# RPi-HAT_BUS-Controller_V0_8.net
KiCad netlist of a schematic drawn in EAGLE
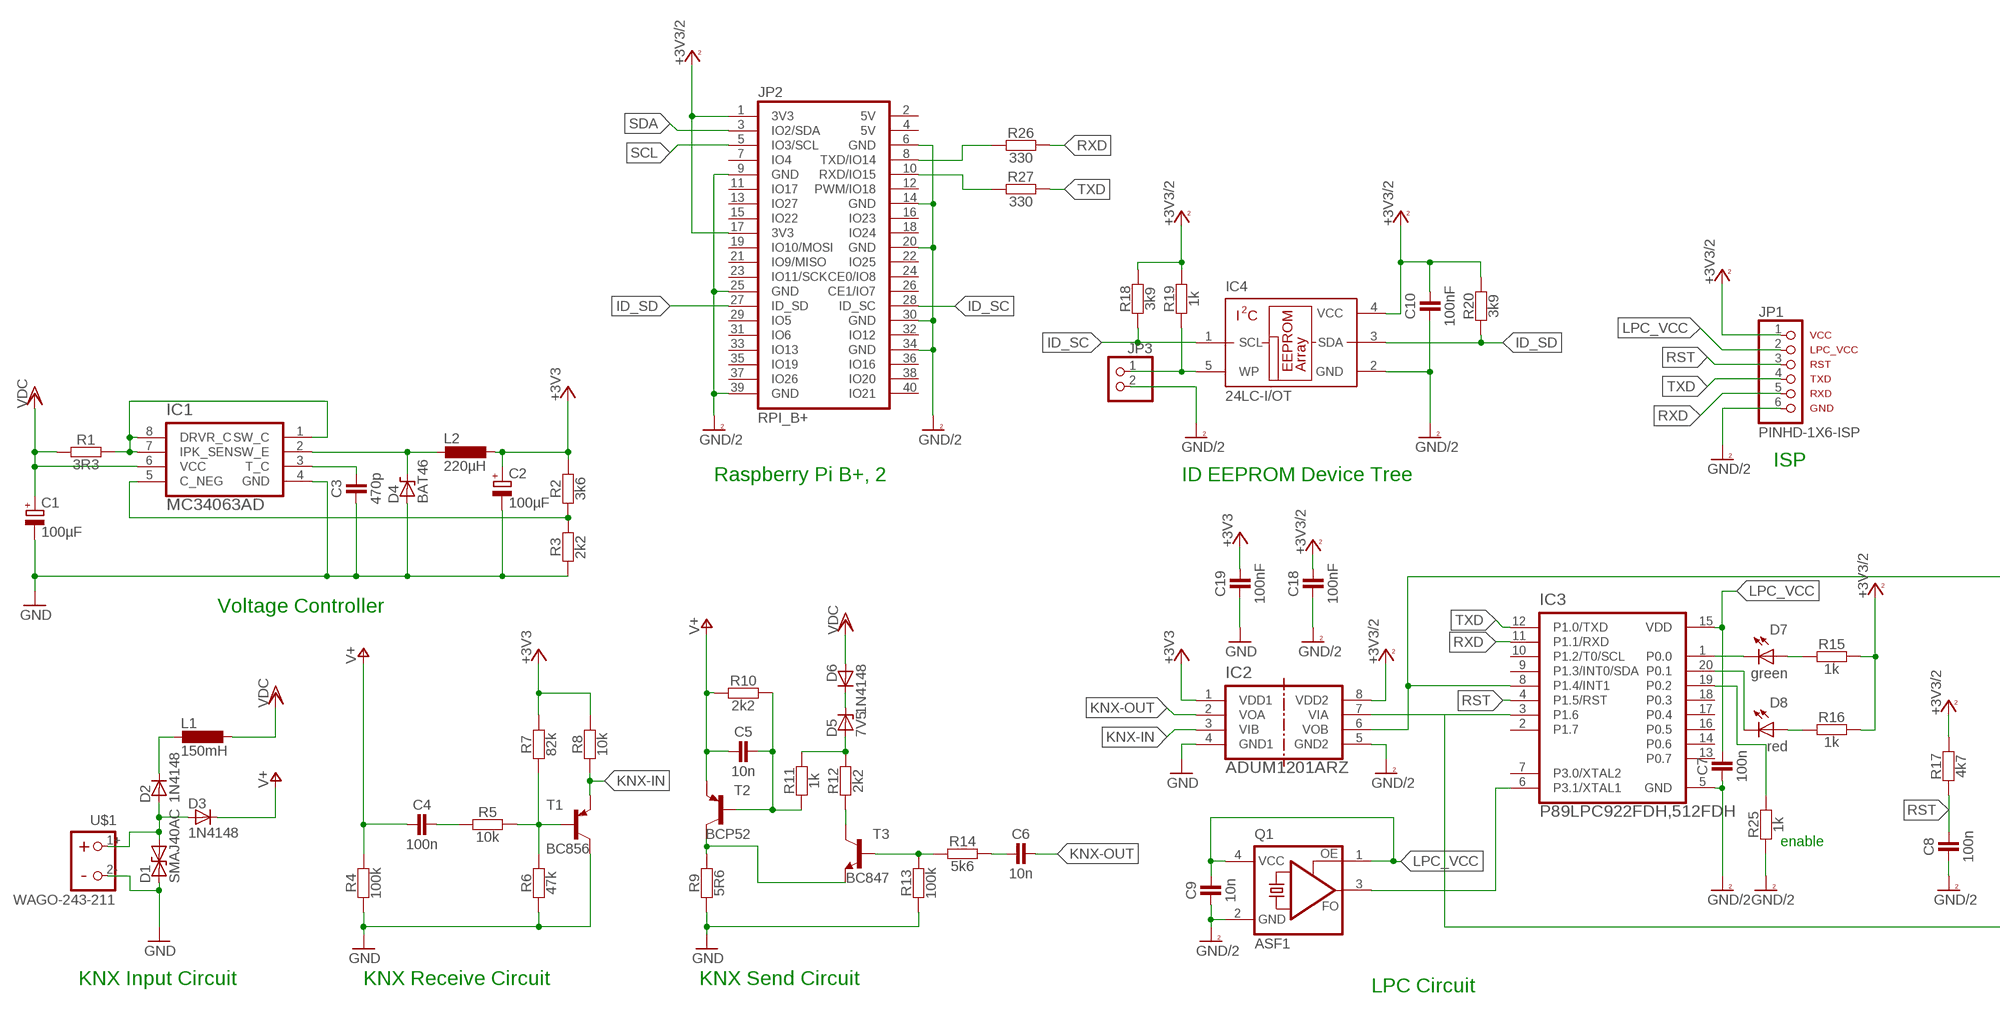
[diagram p0: schematic, sheet 1, part 1 of 2]
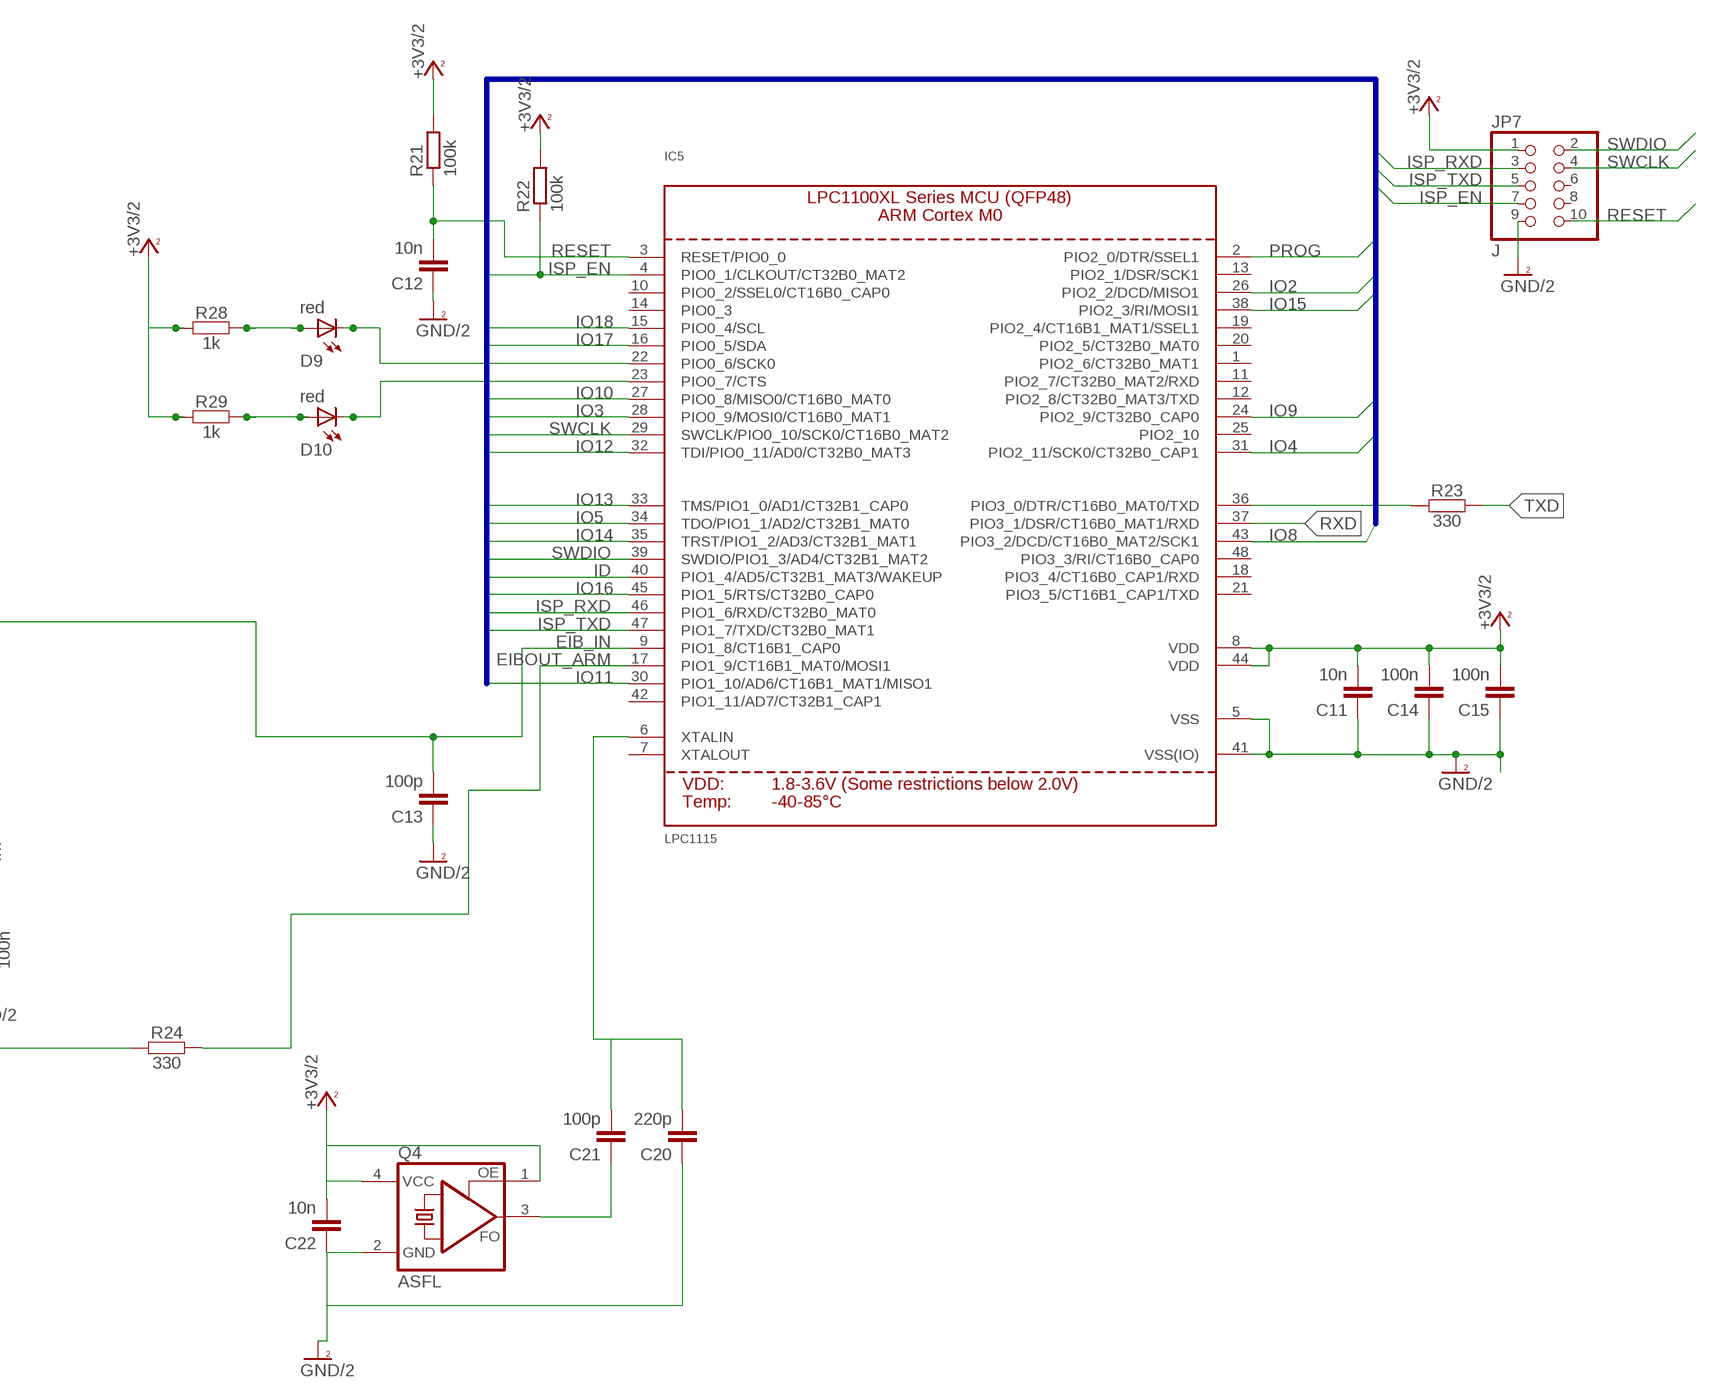
[diagram p1: schematic, sheet 1, part 2 of 2]

(export (version "E")
  (design (tool "Eeschema 10.0.6"))
  (components
    (comp (ref "C1")
      (value "100µF")
      (footprint "eagle-import:PANASONIC_D")
      (libsource (lib "eagle-import") (part "100µF,35V"))
    )
    (comp (ref "C2")
      (value "100µF")
      (footprint "eagle-import:PANASONIC_C")
      (libsource (lib "eagle-import") (part "100µF,6.3V"))
    )
    (comp (ref "C3")
      (value "470p")
      (footprint "eagle-import:R1206")
      (libsource (lib "eagle-import") (part "CAPACITORC1206"))
    )
    (comp (ref "C4")
      (value "100n")
      (footprint "eagle-import:R1206")
      (libsource (lib "eagle-import") (part "CAPACITORC1206"))
    )
    (comp (ref "C5")
      (value "10n")
      (footprint "eagle-import:R1206")
      (libsource (lib "eagle-import") (part "CAPACITORC1206"))
    )
    (comp (ref "C6")
      (value "10n")
      (footprint "eagle-import:R1206")
      (libsource (lib "eagle-import") (part "CAPACITORC1206"))
    )
    (comp (ref "C7")
      (value "100n")
      (footprint "eagle-import:R1206")
      (libsource (lib "eagle-import") (part "CAPACITORC1206"))
    )
    (comp (ref "C8")
      (value "100n")
      (footprint "eagle-import:R1206")
      (libsource (lib "eagle-import") (part "CAPACITORC1206"))
    )
    (comp (ref "C9")
      (value "10n")
      (footprint "eagle-import:R1206")
      (libsource (lib "eagle-import") (part "CAPACITORC1206"))
    )
    (comp (ref "C10")
      (value "100nF")
      (footprint "eagle-import:R1206")
      (libsource (lib "eagle-import") (part "CAPACITORC1206"))
    )
    (comp (ref "C11")
      (value "10n")
      (footprint "eagle-import:C1206")
      (libsource (lib "eagle-import") (part "C-EUC1206"))
    )
    (comp (ref "C12")
      (value "10n")
      (footprint "eagle-import:C1206")
      (libsource (lib "eagle-import") (part "C-EUC1206"))
    )
    (comp (ref "C13")
      (value "100p")
      (footprint "eagle-import:C1206")
      (libsource (lib "eagle-import") (part "C-EUC1206"))
    )
    (comp (ref "C14")
      (value "100n")
      (footprint "eagle-import:C1206")
      (libsource (lib "eagle-import") (part "C-EUC1206"))
    )
    (comp (ref "C15")
      (value "100n")
      (footprint "eagle-import:C1206")
      (libsource (lib "eagle-import") (part "C-EUC1206"))
    )
    (comp (ref "C18")
      (value "100nF")
      (footprint "eagle-import:R1206")
      (libsource (lib "eagle-import") (part "CAPACITORC1206"))
    )
    (comp (ref "C19")
      (value "100nF")
      (footprint "eagle-import:R1206")
      (libsource (lib "eagle-import") (part "CAPACITORC1206"))
    )
    (comp (ref "C20")
      (value "220p")
      (footprint "eagle-import:C1206")
      (libsource (lib "eagle-import") (part "C-EUC1206"))
    )
    (comp (ref "C21")
      (value "100p")
      (footprint "eagle-import:C1206")
      (libsource (lib "eagle-import") (part "C-EUC1206"))
    )
    (comp (ref "C22")
      (value "10n")
      (footprint "eagle-import:C1206")
      (libsource (lib "eagle-import") (part "C-EUC1206"))
    )
    (comp (ref "D1")
      (value "SMAJ40AC")
      (footprint "eagle-import:DO-214AC")
      (libsource (lib "eagle-import") (part "SMAJ40AC"))
    )
    (comp (ref "D2")
      (value "1N4148")
      (footprint "eagle-import:MINIMELF")
      (libsource (lib "eagle-import") (part "1N4148MINIMELF"))
    )
    (comp (ref "D3")
      (value "1N4148")
      (footprint "eagle-import:MINIMELF")
      (libsource (lib "eagle-import") (part "1N4148MINIMELF"))
    )
    (comp (ref "D4")
      (value "BAT46")
      (footprint "eagle-import:MINIMELF")
      (libsource (lib "eagle-import") (part "BAT46"))
    )
    (comp (ref "D5")
      (value "7V5")
      (footprint "eagle-import:MINIMELF")
      (libsource (lib "eagle-import") (part "Z-DIODE"))
    )
    (comp (ref "D6")
      (value "1N4148")
      (footprint "eagle-import:MINIMELF")
      (libsource (lib "eagle-import") (part "Diode_for_Selfbus-Projects_1N4148MINIMELF"))
    )
    (comp (ref "D7")
      (value "green")
      (footprint "eagle-import:CHIPLED_1206")
      (libsource (lib "eagle-import") (part "LED1206"))
    )
    (comp (ref "D8")
      (value "red")
      (footprint "eagle-import:CHIPLED_1206")
      (libsource (lib "eagle-import") (part "LED1206"))
    )
    (comp (ref "D9")
      (value "red")
      (footprint "eagle-import:CHIPLED_1206")
      (libsource (lib "eagle-import") (part "LED1206"))
    )
    (comp (ref "D10")
      (value "red")
      (footprint "eagle-import:CHIPLED_1206")
      (libsource (lib "eagle-import") (part "LED1206"))
    )
    (comp (ref "IC1")
      (value "MC34063AD")
      (footprint "eagle-import:SOIC127P600X175-8N")
      (libsource (lib "eagle-import") (part "MC34063AD"))
    )
    (comp (ref "IC2")
      (value "ADUM1201ARZ")
      (footprint "eagle-import:SOIC127P600X175-8N")
      (libsource (lib "eagle-import") (part "ADUM1201ARZ"))
    )
    (comp (ref "IC3")
      (value "P89LPC922FDH,512FDH")
      (footprint "eagle-import:SOP65P640X110-20N")
      (fields (field (name "MPN") "P89LPC922FDH,512"))
      (libsource (lib "eagle-import") (part "P89LPC922FDH,512FDH"))
    )
    (comp (ref "IC4")
      (value "24LC-I/OT")
      (footprint "eagle-import:SOT23-5")
      (libsource (lib "eagle-import") (part "24LC-I/OT"))
    )
    (comp (ref "IC5")
      (value "LPC1115")
      (footprint "eagle-import:LQFP48")
      (libsource (lib "eagle-import") (part "LPC1113/4/5_QFP48_XLSERIES"))
    )
    (comp (ref "JP1")
      (value "PINHD-1X6-ISP")
      (footprint "eagle-import:1X06")
      (libsource (lib "eagle-import") (part "PINHD-1X6-ISP"))
    )
    (comp (ref "JP2")
      (value "RPI_B+")
      (footprint "eagle-import:RPI-B+HAT")
      (libsource (lib "eagle-import") (part "RPI_B+"))
    )
    (comp (ref "JP3")
      (value "PINHD-1X2")
      (footprint "eagle-import:1X02")
      (libsource (lib "eagle-import") (part "PINHD-1X2"))
    )
    (comp (ref "JP7")
      (value "J")
      (footprint "eagle-import:2X05M")
      (libsource (lib "eagle-import") (part "PINHD-2X05_2.00"))
    )
    (comp (ref "L1")
      (value "150mH")
      (footprint "eagle-import:11P-L1")
      (libsource (lib "eagle-import") (part "150MH-L11PL1"))
    )
    (comp (ref "L2")
      (value "220µH")
      (footprint "eagle-import:2200-11.43")
      (libsource (lib "eagle-import") (part "220µH-SMCC11.43"))
    )
    (comp (ref "Q1")
      (value "ASF1")
      (footprint "eagle-import:ASF")
      (libsource (lib "eagle-import") (part "ASF1"))
    )
    (comp (ref "Q4")
      (value "ASFL")
      (footprint "eagle-import:ASF")
      (fields (field (name "MPN") "ASFLM1-50.000MHZ-C-T"))
      (libsource (lib "eagle-import") (part "crystal_ASFL"))
    )
    (comp (ref "R1")
      (value "3R3")
      (footprint "eagle-import:R1206")
      (libsource (lib "eagle-import") (part "RESISTORR1206"))
    )
    (comp (ref "R2")
      (value "3k6")
      (footprint "eagle-import:R1206")
      (libsource (lib "eagle-import") (part "RESISTORR1206"))
    )
    (comp (ref "R3")
      (value "2k2")
      (footprint "eagle-import:R1206")
      (libsource (lib "eagle-import") (part "RESISTORR1206"))
    )
    (comp (ref "R4")
      (value "100k")
      (footprint "eagle-import:R1206")
      (libsource (lib "eagle-import") (part "RESISTORR1206"))
    )
    (comp (ref "R5")
      (value "10k")
      (footprint "eagle-import:R1206")
      (libsource (lib "eagle-import") (part "RESISTORR1206"))
    )
    (comp (ref "R6")
      (value "47k")
      (footprint "eagle-import:R1206")
      (libsource (lib "eagle-import") (part "RESISTORR1206"))
    )
    (comp (ref "R7")
      (value "82k")
      (footprint "eagle-import:R1206")
      (libsource (lib "eagle-import") (part "RESISTORR1206"))
    )
    (comp (ref "R8")
      (value "10k")
      (footprint "eagle-import:R1206")
      (libsource (lib "eagle-import") (part "RESISTORR1206"))
    )
    (comp (ref "R9")
      (value "5R6")
      (footprint "eagle-import:R1206")
      (libsource (lib "eagle-import") (part "RESISTORR1206"))
    )
    (comp (ref "R10")
      (value "2k2")
      (footprint "eagle-import:R1206")
      (libsource (lib "eagle-import") (part "RESISTORR1206"))
    )
    (comp (ref "R11")
      (value "1k")
      (footprint "eagle-import:R1206")
      (libsource (lib "eagle-import") (part "RESISTORR1206"))
    )
    (comp (ref "R12")
      (value "2k2")
      (footprint "eagle-import:R1206")
      (libsource (lib "eagle-import") (part "RESISTORR1206"))
    )
    (comp (ref "R13")
      (value "100k")
      (footprint "eagle-import:R1206")
      (libsource (lib "eagle-import") (part "RESISTORR1206"))
    )
    (comp (ref "R14")
      (value "5k6")
      (footprint "eagle-import:R1206")
      (libsource (lib "eagle-import") (part "RESISTORR1206"))
    )
    (comp (ref "R15")
      (value "1k")
      (footprint "eagle-import:R1206")
      (libsource (lib "eagle-import") (part "RESISTORR1206"))
    )
    (comp (ref "R16")
      (value "1k")
      (footprint "eagle-import:R1206")
      (libsource (lib "eagle-import") (part "RESISTORR1206"))
    )
    (comp (ref "R17")
      (value "4k7")
      (footprint "eagle-import:R1206")
      (libsource (lib "eagle-import") (part "RESISTORR1206"))
    )
    (comp (ref "R18")
      (value "3k9")
      (footprint "eagle-import:R1206")
      (libsource (lib "eagle-import") (part "RESISTORR1206"))
    )
    (comp (ref "R19")
      (value "1k")
      (footprint "eagle-import:R1206")
      (libsource (lib "eagle-import") (part "RESISTORR1206"))
    )
    (comp (ref "R20")
      (value "3k9")
      (footprint "eagle-import:R1206")
      (libsource (lib "eagle-import") (part "RESISTORR1206"))
    )
    (comp (ref "R21")
      (value "100k")
      (footprint "eagle-import:R1206")
      (libsource (lib "eagle-import") (part "R-EU_R1206"))
    )
    (comp (ref "R22")
      (value "100k")
      (footprint "eagle-import:R1206")
      (libsource (lib "eagle-import") (part "R-EU_R1206"))
    )
    (comp (ref "R23")
      (value "330")
      (footprint "eagle-import:R1206")
      (libsource (lib "eagle-import") (part "RESISTORR1206"))
    )
    (comp (ref "R24")
      (value "330")
      (footprint "eagle-import:R1206")
      (libsource (lib "eagle-import") (part "RESISTORR1206"))
    )
    (comp (ref "R25")
      (value "1k")
      (footprint "eagle-import:R1206")
      (libsource (lib "eagle-import") (part "RESISTORR1206"))
    )
    (comp (ref "R26")
      (value "330")
      (footprint "eagle-import:R1206")
      (libsource (lib "eagle-import") (part "RESISTORR1206"))
    )
    (comp (ref "R27")
      (value "330")
      (footprint "eagle-import:R1206")
      (libsource (lib "eagle-import") (part "RESISTORR1206"))
    )
    (comp (ref "R28")
      (value "1k")
      (footprint "eagle-import:R1206")
      (libsource (lib "eagle-import") (part "RESISTORR1206"))
    )
    (comp (ref "R29")
      (value "1k")
      (footprint "eagle-import:R1206")
      (libsource (lib "eagle-import") (part "RESISTORR1206"))
    )
    (comp (ref "T1")
      (value "BC856")
      (footprint "eagle-import:SOT23")
      (libsource (lib "eagle-import") (part "PNPBC856"))
    )
    (comp (ref "T2")
      (value "BCP52")
      (footprint "eagle-import:SOT223")
      (libsource (lib "eagle-import") (part "PNPBCP52"))
    )
    (comp (ref "T3")
      (value "BC847")
      (footprint "eagle-import:SOT23")
      (libsource (lib "eagle-import") (part "NPN-BC847"))
    )
    (comp (ref "U$1")
      (value "WAGO-243-211")
      (footprint "eagle-import:WAGO-243-211")
      (libsource (lib "eagle-import") (part "WAGO-243-211"))
    )
  )
  (nets
    (net (code "1") (name "+3V3") (class "Default")
      (node (ref "C19") (pin "2") (pinfunction "2_2") (pintype "passive"))
      (node (ref "C2") (pin "+") (pinfunction "+_+") (pintype "passive"))
      (node (ref "IC2") (pin "1") (pinfunction "VDD1_1") (pintype "power_in"))
      (node (ref "L2") (pin "1") (pinfunction "1_1") (pintype "passive"))
      (node (ref "R2") (pin "2") (pinfunction "2_2") (pintype "passive"))
      (node (ref "R7") (pin "2") (pinfunction "2_2") (pintype "passive"))
      (node (ref "R8") (pin "2") (pinfunction "2_2") (pintype "passive"))
    )
    (net (code "2") (name "+3V3{slash}2") (class "Default")
      (node (ref "C10") (pin "2") (pinfunction "2_2") (pintype "passive"))
      (node (ref "C11") (pin "2") (pinfunction "2_2") (pintype "passive"))
      (node (ref "C14") (pin "2") (pinfunction "2_2") (pintype "passive"))
      (node (ref "C15") (pin "2") (pinfunction "2_2") (pintype "passive"))
      (node (ref "C18") (pin "2") (pinfunction "2_2") (pintype "passive"))
      (node (ref "C22") (pin "2") (pinfunction "2_2") (pintype "passive"))
      (node (ref "IC2") (pin "8") (pinfunction "VDD2_8") (pintype "power_in"))
      (node (ref "IC4") (pin "4") (pinfunction "VCC_4") (pintype "power_in"))
      (node (ref "IC5") (pin "44") (pinfunction "VDD_44") (pintype "power_in"))
      (node (ref "IC5") (pin "8") (pinfunction "VDD_8") (pintype "power_in"))
      (node (ref "JP1") (pin "1") (pinfunction "1_1") (pintype "passive"))
      (node (ref "JP2") (pin "1") (pinfunction "3V3_1") (pintype "passive"))
      (node (ref "JP2") (pin "17") (pinfunction "3V3_17") (pintype "passive"))
      (node (ref "JP7") (pin "1") (pinfunction "1_1") (pintype "passive"))
      (node (ref "Q4") (pin "1") (pinfunction "OE_1") (pintype "input"))
      (node (ref "Q4") (pin "4") (pinfunction "VCC_4") (pintype "power_in"))
      (node (ref "R15") (pin "2") (pinfunction "2_2") (pintype "passive"))
      (node (ref "R16") (pin "2") (pinfunction "2_2") (pintype "passive"))
      (node (ref "R17") (pin "2") (pinfunction "2_2") (pintype "passive"))
      (node (ref "R18") (pin "2") (pinfunction "2_2") (pintype "passive"))
      (node (ref "R19") (pin "2") (pinfunction "2_2") (pintype "passive"))
      (node (ref "R20") (pin "2") (pinfunction "2_2") (pintype "passive"))
      (node (ref "R21") (pin "2") (pinfunction "2_2") (pintype "passive"))
      (node (ref "R22") (pin "2") (pinfunction "2_2") (pintype "passive"))
      (node (ref "R28") (pin "1") (pinfunction "1_1") (pintype "passive"))
      (node (ref "R29") (pin "1") (pinfunction "1_1") (pintype "passive"))
    )
    (net (code "3") (name "/EIBOUT_ARM") (class "Default")
      (node (ref "IC5") (pin "17") (pinfunction "PIO1_9/CT16B1_MAT0/MOSI1_17") (pintype "bidirectional"))
      (node (ref "R24") (pin "2") (pinfunction "2_2") (pintype "passive"))
    )
    (net (code "4") (name "/EIB_IN") (class "Default")
      (node (ref "C13") (pin "2") (pinfunction "2_2") (pintype "passive"))
      (node (ref "IC2") (pin "6") (pinfunction "VOB_6") (pintype "output"))
      (node (ref "IC3") (pin "8") (pinfunction "P1.4/INT1_8") (pintype "bidirectional"))
      (node (ref "IC5") (pin "9") (pinfunction "PIO1_8/CT16B1_CAP0_9") (pintype "bidirectional"))
    )
    (net (code "5") (name "/ID") (class "Default")
      (node (ref "IC5") (pin "40") (pinfunction "PIO1_4/AD5/CT32B1_MAT3/WAKEUP_40") (pintype "bidirectional"))
    )
    (net (code "6") (name "/IO2") (class "Default")
      (node (ref "IC5") (pin "26") (pinfunction "PIO2_2/DCD/MISO1_26") (pintype "bidirectional"))
    )
    (net (code "7") (name "/IO3") (class "Default")
      (node (ref "IC5") (pin "28") (pinfunction "PIO0_9/MOSI0/CT16B0_MAT1_28") (pintype "bidirectional"))
    )
    (net (code "8") (name "/IO4") (class "Default")
      (node (ref "IC5") (pin "31") (pinfunction "PIO2_11/SCK0/CT32B0_CAP1_31") (pintype "bidirectional"))
    )
    (net (code "9") (name "/IO5") (class "Default")
      (node (ref "IC5") (pin "34") (pinfunction "TDO/PIO1_1/AD2/CT32B1_MAT0_34") (pintype "bidirectional"))
    )
    (net (code "10") (name "/IO8") (class "Default")
      (node (ref "IC5") (pin "43") (pinfunction "PIO3_2/DCD/CT16B0_MAT2/SCK1_43") (pintype "bidirectional"))
    )
    (net (code "11") (name "/IO9") (class "Default")
      (node (ref "IC5") (pin "24") (pinfunction "PIO2_9/CT32B0_CAP0_24") (pintype "bidirectional"))
    )
    (net (code "12") (name "/IO10") (class "Default")
      (node (ref "IC5") (pin "27") (pinfunction "PIO0_8/MISO0/CT16B0_MAT0_27") (pintype "bidirectional"))
    )
    (net (code "13") (name "/IO11") (class "Default")
      (node (ref "IC5") (pin "30") (pinfunction "PIO1_10/AD6/CT16B1_MAT1/MISO1_30") (pintype "bidirectional"))
    )
    (net (code "14") (name "/IO12") (class "Default")
      (node (ref "IC5") (pin "32") (pinfunction "TDI/PIO0_11/AD0/CT32B0_MAT3_32") (pintype "bidirectional"))
    )
    (net (code "15") (name "/IO13") (class "Default")
      (node (ref "IC5") (pin "33") (pinfunction "TMS/PIO1_0/AD1/CT32B1_CAP0_33") (pintype "bidirectional"))
    )
    (net (code "16") (name "/IO14") (class "Default")
      (node (ref "IC5") (pin "35") (pinfunction "TRST/PIO1_2/AD3/CT32B1_MAT1_35") (pintype "bidirectional"))
    )
    (net (code "17") (name "/IO15") (class "Default")
      (node (ref "IC5") (pin "38") (pinfunction "PIO2_3/RI/MOSI1_38") (pintype "bidirectional"))
    )
    (net (code "18") (name "/IO16") (class "Default")
      (node (ref "IC5") (pin "45") (pinfunction "PIO1_5/RTS/CT32B0_CAP0_45") (pintype "bidirectional"))
    )
    (net (code "19") (name "/IO17") (class "Default")
      (node (ref "IC5") (pin "16") (pinfunction "PIO0_5/SDA_16") (pintype "bidirectional"))
    )
    (net (code "20") (name "/IO18") (class "Default")
      (node (ref "IC5") (pin "15") (pinfunction "PIO0_4/SCL_15") (pintype "bidirectional"))
    )
    (net (code "21") (name "/ISP_EN") (class "Default")
      (node (ref "IC5") (pin "4") (pinfunction "PIO0_1/CLKOUT/CT32B0_MAT2_4") (pintype "bidirectional"))
      (node (ref "JP7") (pin "7") (pinfunction "7_7") (pintype "passive"))
      (node (ref "R22") (pin "1") (pinfunction "1_1") (pintype "passive"))
    )
    (net (code "22") (name "/ISP_RXD") (class "Default")
      (node (ref "IC5") (pin "46") (pinfunction "PIO1_6/RXD/CT32B0_MAT0_46") (pintype "bidirectional"))
      (node (ref "JP7") (pin "3") (pinfunction "3_3") (pintype "passive"))
    )
    (net (code "23") (name "/ISP_TXD") (class "Default")
      (node (ref "IC5") (pin "47") (pinfunction "PIO1_7/TXD/CT32B0_MAT1_47") (pintype "bidirectional"))
      (node (ref "JP7") (pin "5") (pinfunction "5_5") (pintype "passive"))
    )
    (net (code "24") (name "/PROG") (class "Default")
      (node (ref "IC5") (pin "2") (pinfunction "PIO2_0/DTR/SSEL1_2") (pintype "bidirectional"))
    )
    (net (code "25") (name "/RESET") (class "Default")
      (node (ref "C12") (pin "2") (pinfunction "2_2") (pintype "passive"))
      (node (ref "IC5") (pin "3") (pinfunction "RESET/PIO0_0_3") (pintype "bidirectional"))
      (node (ref "JP7") (pin "10") (pinfunction "10_10") (pintype "passive"))
      (node (ref "R21") (pin "1") (pinfunction "1_1") (pintype "passive"))
    )
    (net (code "26") (name "/SWCLK") (class "Default")
      (node (ref "IC5") (pin "29") (pinfunction "SWCLK/PIO0_10/SCK0/CT16B0_MAT2_29") (pintype "bidirectional"))
      (node (ref "JP7") (pin "4") (pinfunction "4_4") (pintype "passive"))
    )
    (net (code "27") (name "/SWDIO") (class "Default")
      (node (ref "IC5") (pin "39") (pinfunction "SWDIO/PIO1_3/AD4/CT32B1_MAT2_39") (pintype "bidirectional"))
      (node (ref "JP7") (pin "2") (pinfunction "2_2") (pintype "passive"))
    )
    (net (code "28") (name "GND") (class "Default")
      (node (ref "C1") (pin "-") (pinfunction "-_-") (pintype "passive"))
      (node (ref "C19") (pin "1") (pinfunction "1_1") (pintype "passive"))
      (node (ref "C2") (pin "-") (pinfunction "-_-") (pintype "passive"))
      (node (ref "C3") (pin "1") (pinfunction "1_1") (pintype "passive"))
      (node (ref "D1") (pin "A") (pinfunction "A_A") (pintype "passive"))
      (node (ref "D4") (pin "A") (pinfunction "A_A") (pintype "passive"))
      (node (ref "IC1") (pin "4") (pinfunction "GND_4") (pintype "passive"))
      (node (ref "IC2") (pin "4") (pinfunction "GND1_4") (pintype "passive"))
      (node (ref "R13") (pin "1") (pinfunction "1_1") (pintype "passive"))
      (node (ref "R3") (pin "1") (pinfunction "1_1") (pintype "passive"))
      (node (ref "R4") (pin "1") (pinfunction "1_1") (pintype "passive"))
      (node (ref "R6") (pin "1") (pinfunction "1_1") (pintype "passive"))
      (node (ref "R9") (pin "1") (pinfunction "1_1") (pintype "passive"))
      (node (ref "T1") (pin "3") (pinfunction "C_3") (pintype "passive"))
      (node (ref "U$1") (pin "2-") (pinfunction "2-_2-") (pintype "passive"))
    )
    (net (code "29") (name "GND{slash}2") (class "Default")
      (node (ref "C10") (pin "1") (pinfunction "1_1") (pintype "passive"))
      (node (ref "C11") (pin "1") (pinfunction "1_1") (pintype "passive"))
      (node (ref "C12") (pin "1") (pinfunction "1_1") (pintype "passive"))
      (node (ref "C13") (pin "1") (pinfunction "1_1") (pintype "passive"))
      (node (ref "C14") (pin "1") (pinfunction "1_1") (pintype "passive"))
      (node (ref "C15") (pin "1") (pinfunction "1_1") (pintype "passive"))
      (node (ref "C18") (pin "1") (pinfunction "1_1") (pintype "passive"))
      (node (ref "C20") (pin "1") (pinfunction "1_1") (pintype "passive"))
      (node (ref "C22") (pin "1") (pinfunction "1_1") (pintype "passive"))
      (node (ref "C7") (pin "1") (pinfunction "1_1") (pintype "passive"))
      (node (ref "C8") (pin "1") (pinfunction "1_1") (pintype "passive"))
      (node (ref "C9") (pin "1") (pinfunction "1_1") (pintype "passive"))
      (node (ref "IC2") (pin "5") (pinfunction "GND2_5") (pintype "passive"))
      (node (ref "IC3") (pin "5") (pinfunction "GND_5") (pintype "passive"))
      (node (ref "IC4") (pin "2") (pinfunction "GND_2") (pintype "power_in"))
      (node (ref "IC5") (pin "41") (pinfunction "VSS(IO)_41") (pintype "power_in"))
      (node (ref "IC5") (pin "5") (pinfunction "VSS_5") (pintype "power_in"))
      (node (ref "JP1") (pin "6") (pinfunction "6_6") (pintype "passive"))
      (node (ref "JP2") (pin "14") (pinfunction "GND_14") (pintype "passive"))
      (node (ref "JP2") (pin "20") (pinfunction "GND_20") (pintype "passive"))
      (node (ref "JP2") (pin "25") (pinfunction "GND_25") (pintype "passive"))
      (node (ref "JP2") (pin "30") (pinfunction "GND_30") (pintype "bidirectional"))
      (node (ref "JP2") (pin "34") (pinfunction "GND_34") (pintype "bidirectional"))
      (node (ref "JP2") (pin "39") (pinfunction "GND_39") (pintype "bidirectional"))
      (node (ref "JP2") (pin "6") (pinfunction "GND_6") (pintype "passive"))
      (node (ref "JP2") (pin "9") (pinfunction "GND_9") (pintype "passive"))
      (node (ref "JP3") (pin "2") (pinfunction "2_2") (pintype "passive"))
      (node (ref "JP7") (pin "9") (pinfunction "9_9") (pintype "passive"))
      (node (ref "Q1") (pin "2") (pinfunction "GND_2") (pintype "power_in"))
      (node (ref "Q4") (pin "2") (pinfunction "GND_2") (pintype "power_in"))
      (node (ref "R25") (pin "1") (pinfunction "1_1") (pintype "passive"))
    )
    (net (code "30") (name "ID_SC") (class "Default")
      (node (ref "IC4") (pin "1") (pinfunction "SCL_1") (pintype "bidirectional"))
      (node (ref "JP2") (pin "28") (pinfunction "ID_SC_28") (pintype "bidirectional"))
      (node (ref "R18") (pin "1") (pinfunction "1_1") (pintype "passive"))
    )
    (net (code "31") (name "ID_SD") (class "Default")
      (node (ref "IC4") (pin "3") (pinfunction "SDA_3") (pintype "bidirectional"))
      (node (ref "JP2") (pin "27") (pinfunction "ID_SD_27") (pintype "bidirectional"))
      (node (ref "R20") (pin "1") (pinfunction "1_1") (pintype "passive"))
    )
    (net (code "32") (name "KNX-IN") (class "Default")
      (node (ref "IC2") (pin "3") (pinfunction "VIB_3") (pintype "input"))
      (node (ref "R8") (pin "1") (pinfunction "1_1") (pintype "passive"))
      (node (ref "T1") (pin "2") (pinfunction "E_2") (pintype "passive"))
    )
    (net (code "33") (name "KNX-OUT") (class "Default")
      (node (ref "C6") (pin "2") (pinfunction "2_2") (pintype "passive"))
      (node (ref "IC2") (pin "2") (pinfunction "VOA_2") (pintype "output"))
    )
    (net (code "34") (name "LPC_VCC") (class "Default")
      (node (ref "C7") (pin "2") (pinfunction "2_2") (pintype "passive"))
      (node (ref "C9") (pin "2") (pinfunction "2_2") (pintype "passive"))
      (node (ref "IC3") (pin "15") (pinfunction "VDD_15") (pintype "power_in"))
      (node (ref "JP1") (pin "2") (pinfunction "2_2") (pintype "passive"))
      (node (ref "Q1") (pin "1") (pinfunction "OE_1") (pintype "input"))
      (node (ref "Q1") (pin "4") (pinfunction "VCC_4") (pintype "power_in"))
    )
    (net (code "35") (name "Net-(C4-Pad2)") (class "Default")
      (node (ref "C4") (pin "2") (pinfunction "2_2") (pintype "passive"))
      (node (ref "R5") (pin "1") (pinfunction "1_1") (pintype "passive"))
    )
    (net (code "36") (name "Net-(C6-Pad1)") (class "Default")
      (node (ref "C6") (pin "1") (pinfunction "1_1") (pintype "passive"))
      (node (ref "R14") (pin "2") (pinfunction "2_2") (pintype "passive"))
    )
    (net (code "37") (name "Net-(D1-PadC)") (class "Default")
      (node (ref "D1") (pin "C") (pinfunction "C_C") (pintype "passive"))
      (node (ref "D2") (pin "A") (pinfunction "A_A") (pintype "passive"))
      (node (ref "D3") (pin "A") (pinfunction "A_A") (pintype "passive"))
      (node (ref "U$1") (pin "1+") (pinfunction "1+_1+") (pintype "passive"))
    )
    (net (code "38") (name "Net-(D2-PadC)") (class "Default")
      (node (ref "D2") (pin "C") (pinfunction "C_C") (pintype "passive"))
      (node (ref "L1") (pin "2") (pinfunction "2_2") (pintype "passive"))
    )
    (net (code "39") (name "Net-(D5-PadA)") (class "Default")
      (node (ref "D5") (pin "A") (pinfunction "A_A") (pintype "passive"))
      (node (ref "R11") (pin "2") (pinfunction "2_2") (pintype "passive"))
      (node (ref "R12") (pin "2") (pinfunction "2_2") (pintype "passive"))
    )
    (net (code "40") (name "Net-(D5-PadC)") (class "Default")
      (node (ref "D5") (pin "C") (pinfunction "C_C") (pintype "passive"))
      (node (ref "D6") (pin "C") (pinfunction "C_C") (pintype "passive"))
    )
    (net (code "41") (name "Net-(D7-PadA)") (class "Default")
      (node (ref "D7") (pin "A") (pinfunction "A_A") (pintype "passive"))
      (node (ref "R15") (pin "1") (pinfunction "1_1") (pintype "passive"))
    )
    (net (code "42") (name "Net-(D8-PadA)") (class "Default")
      (node (ref "D8") (pin "A") (pinfunction "A_A") (pintype "passive"))
      (node (ref "R16") (pin "1") (pinfunction "1_1") (pintype "passive"))
    )
    (net (code "43") (name "Net-(D9-PadA)") (class "Default")
      (node (ref "D9") (pin "A") (pinfunction "A_A") (pintype "passive"))
      (node (ref "R28") (pin "2") (pinfunction "2_2") (pintype "passive"))
    )
    (net (code "44") (name "Net-(D10-PadA)") (class "Default")
      (node (ref "D10") (pin "A") (pinfunction "A_A") (pintype "passive"))
      (node (ref "R29") (pin "2") (pinfunction "2_2") (pintype "passive"))
    )
    (net (code "45") (name "Net-(IC1-C_NEG)") (class "Default")
      (node (ref "IC1") (pin "5") (pinfunction "C_NEG_5") (pintype "input"))
      (node (ref "R2") (pin "1") (pinfunction "1_1") (pintype "passive"))
      (node (ref "R3") (pin "2") (pinfunction "2_2") (pintype "passive"))
    )
    (net (code "46") (name "Net-(IC1-DRVR_C)") (class "Default")
      (node (ref "IC1") (pin "1") (pinfunction "SW_C_1") (pintype "output"))
      (node (ref "IC1") (pin "7") (pinfunction "IPK_SEN_7") (pintype "input"))
      (node (ref "IC1") (pin "8") (pinfunction "DRVR_C_8") (pintype "input"))
      (node (ref "R1") (pin "2") (pinfunction "2_2") (pintype "passive"))
    )
    (net (code "47") (name "Net-(IC1-SW_E)") (class "Default")
      (node (ref "D4") (pin "C") (pinfunction "C_C") (pintype "passive"))
      (node (ref "IC1") (pin "2") (pinfunction "SW_E_2") (pintype "output"))
      (node (ref "L2") (pin "2") (pinfunction "2_2") (pintype "passive"))
    )
    (net (code "48") (name "Net-(IC1-T_C)") (class "Default")
      (node (ref "C3") (pin "2") (pinfunction "2_2") (pintype "passive"))
      (node (ref "IC1") (pin "3") (pinfunction "T_C_3") (pintype "output"))
    )
    (net (code "49") (name "Net-(IC2-VIA)") (class "Default")
      (node (ref "IC2") (pin "7") (pinfunction "VIA_7") (pintype "input"))
      (node (ref "IC3") (pin "3") (pinfunction "P1.6_3") (pintype "bidirectional"))
      (node (ref "R24") (pin "1") (pinfunction "1_1") (pintype "passive"))
    )
    (net (code "50") (name "Net-(IC3-P0.0)") (class "Default")
      (node (ref "D7") (pin "C") (pinfunction "C_C") (pintype "passive"))
      (node (ref "IC3") (pin "1") (pinfunction "P0.0_1") (pintype "bidirectional"))
    )
    (net (code "51") (name "Net-(IC3-P0.1)") (class "Default")
      (node (ref "D8") (pin "C") (pinfunction "C_C") (pintype "passive"))
      (node (ref "IC3") (pin "20") (pinfunction "P0.1_20") (pintype "bidirectional"))
    )
    (net (code "52") (name "Net-(IC3-P0.2)") (class "Default")
      (node (ref "IC3") (pin "19") (pinfunction "P0.2_19") (pintype "bidirectional"))
      (node (ref "R25") (pin "2") (pinfunction "2_2") (pintype "passive"))
    )
    (net (code "53") (name "Net-(IC3-P3.1{slash}XTAL1)") (class "Default")
      (node (ref "IC3") (pin "6") (pinfunction "P3.1/XTAL1_6") (pintype "bidirectional"))
      (node (ref "Q1") (pin "3") (pinfunction "FO_3") (pintype "output"))
    )
    (net (code "54") (name "Net-(IC4-WP)") (class "Default")
      (node (ref "IC4") (pin "5") (pinfunction "WP_5") (pintype "bidirectional"))
      (node (ref "JP3") (pin "1") (pinfunction "1_1") (pintype "passive"))
      (node (ref "R19") (pin "1") (pinfunction "1_1") (pintype "passive"))
    )
    (net (code "55") (name "Net-(IC5-PIO0_6{slash}SCK0)") (class "Default")
      (node (ref "D9") (pin "C") (pinfunction "C_C") (pintype "passive"))
      (node (ref "IC5") (pin "22") (pinfunction "PIO0_6/SCK0_22") (pintype "bidirectional"))
    )
    (net (code "56") (name "Net-(IC5-PIO0_7{slash}CTS)") (class "Default")
      (node (ref "D10") (pin "C") (pinfunction "C_C") (pintype "passive"))
      (node (ref "IC5") (pin "23") (pinfunction "PIO0_7/CTS_23") (pintype "bidirectional"))
    )
    (net (code "57") (name "Net-(IC5-PIO3_0{slash}DTR{slash}CT16B0_MAT0{slash}TXD)") (class "Default")
      (node (ref "IC5") (pin "36") (pinfunction "PIO3_0/DTR/CT16B0_MAT0/TXD_36") (pintype "bidirectional"))
      (node (ref "R23") (pin "1") (pinfunction "1_1") (pintype "passive"))
    )
    (net (code "58") (name "Net-(IC5-XTALIN)") (class "Default")
      (node (ref "C20") (pin "2") (pinfunction "2_2") (pintype "passive"))
      (node (ref "C21") (pin "2") (pinfunction "2_2") (pintype "passive"))
      (node (ref "IC5") (pin "6") (pinfunction "XTALIN_6") (pintype "input"))
    )
    (net (code "59") (name "Net-(JP2-RXD{slash}IO15)") (class "Default")
      (node (ref "JP2") (pin "10") (pinfunction "RXD/IO15_10") (pintype "passive"))
      (node (ref "R27") (pin "1") (pinfunction "1_1") (pintype "passive"))
    )
    (net (code "60") (name "Net-(JP2-TXD{slash}IO14)") (class "Default")
      (node (ref "JP2") (pin "8") (pinfunction "TXD/IO14_8") (pintype "passive"))
      (node (ref "R26") (pin "1") (pinfunction "1_1") (pintype "passive"))
    )
    (net (code "61") (name "Net-(Q4-FO)") (class "Default")
      (node (ref "C21") (pin "1") (pinfunction "1_1") (pintype "passive"))
      (node (ref "Q4") (pin "3") (pinfunction "FO_3") (pintype "output"))
    )
    (net (code "62") (name "Net-(T1-B)") (class "Default")
      (node (ref "R5") (pin "2") (pinfunction "2_2") (pintype "passive"))
      (node (ref "R6") (pin "2") (pinfunction "2_2") (pintype "passive"))
      (node (ref "R7") (pin "1") (pinfunction "1_1") (pintype "passive"))
      (node (ref "T1") (pin "1") (pinfunction "B_1") (pintype "passive"))
    )
    (net (code "63") (name "Net-(T2-B)") (class "Default")
      (node (ref "C5") (pin "2") (pinfunction "2_2") (pintype "passive"))
      (node (ref "R10") (pin "2") (pinfunction "2_2") (pintype "passive"))
      (node (ref "R11") (pin "1") (pinfunction "1_1") (pintype "passive"))
      (node (ref "T2") (pin "1") (pinfunction "B_1") (pintype "passive"))
    )
    (net (code "64") (name "Net-(T3-B)") (class "Default")
      (node (ref "R13") (pin "2") (pinfunction "2_2") (pintype "passive"))
      (node (ref "R14") (pin "1") (pinfunction "1_1") (pintype "passive"))
      (node (ref "T3") (pin "1") (pinfunction "B_1") (pintype "passive"))
    )
    (net (code "65") (name "Net-(T3-C)") (class "Default")
      (node (ref "R12") (pin "1") (pinfunction "1_1") (pintype "passive"))
      (node (ref "T3") (pin "3") (pinfunction "C_3") (pintype "passive"))
    )
    (net (code "66") (name "Net-(T3-E)") (class "Default")
      (node (ref "R9") (pin "2") (pinfunction "2_2") (pintype "passive"))
      (node (ref "T2") (pin "2") (pinfunction "C_2") (pintype "passive"))
      (node (ref "T2") (pin "4") (pinfunction "C_4") (pintype "passive"))
      (node (ref "T3") (pin "2") (pinfunction "E_2") (pintype "passive"))
    )
    (net (code "67") (name "RST") (class "Default")
      (node (ref "C8") (pin "2") (pinfunction "2_2") (pintype "passive"))
      (node (ref "IC3") (pin "4") (pinfunction "P1.5/RST_4") (pintype "input"))
      (node (ref "JP1") (pin "3") (pinfunction "3_3") (pintype "passive"))
      (node (ref "R17") (pin "1") (pinfunction "1_1") (pintype "passive"))
    )
    (net (code "68") (name "RXD") (class "Default")
      (node (ref "IC3") (pin "11") (pinfunction "P1.1/RXD_11") (pintype "bidirectional"))
      (node (ref "IC5") (pin "37") (pinfunction "PIO3_1/DSR/CT16B0_MAT1/RXD_37") (pintype "bidirectional"))
      (node (ref "JP1") (pin "5") (pinfunction "5_5") (pintype "passive"))
      (node (ref "R26") (pin "2") (pinfunction "2_2") (pintype "passive"))
    )
    (net (code "69") (name "SCL") (class "Default")
      (node (ref "JP2") (pin "5") (pinfunction "IO3/SCL_5") (pintype "passive"))
    )
    (net (code "70") (name "SDA") (class "Default")
      (node (ref "JP2") (pin "3") (pinfunction "IO2/SDA_3") (pintype "passive"))
    )
    (net (code "71") (name "TXD") (class "Default")
      (node (ref "IC3") (pin "12") (pinfunction "P1.0/TXD_12") (pintype "bidirectional"))
      (node (ref "JP1") (pin "4") (pinfunction "4_4") (pintype "passive"))
      (node (ref "R23") (pin "2") (pinfunction "2_2") (pintype "passive"))
      (node (ref "R27") (pin "2") (pinfunction "2_2") (pintype "passive"))
    )
    (net (code "72") (name "V+") (class "Default")
      (node (ref "C4") (pin "1") (pinfunction "1_1") (pintype "passive"))
      (node (ref "C5") (pin "1") (pinfunction "1_1") (pintype "passive"))
      (node (ref "D3") (pin "C") (pinfunction "C_C") (pintype "passive"))
      (node (ref "R10") (pin "1") (pinfunction "1_1") (pintype "passive"))
      (node (ref "R4") (pin "2") (pinfunction "2_2") (pintype "passive"))
      (node (ref "T2") (pin "3") (pinfunction "E_3") (pintype "passive"))
    )
    (net (code "73") (name "VDC") (class "Default")
      (node (ref "C1") (pin "+") (pinfunction "+_+") (pintype "passive"))
      (node (ref "D6") (pin "A") (pinfunction "A_A") (pintype "passive"))
      (node (ref "IC1") (pin "6") (pinfunction "VCC_6") (pintype "power_in"))
      (node (ref "L1") (pin "1") (pinfunction "1_1") (pintype "passive"))
      (node (ref "R1") (pin "1") (pinfunction "1_1") (pintype "passive"))
    )
    (net (code "74") (name "unconnected-(IC3-P0.3-Pad18)") (class "Default")
      (node (ref "IC3") (pin "18") (pinfunction "P0.3_18") (pintype "bidirectional"))
    )
    (net (code "75") (name "unconnected-(IC3-P0.4-Pad17)") (class "Default")
      (node (ref "IC3") (pin "17") (pinfunction "P0.4_17") (pintype "bidirectional"))
    )
    (net (code "76") (name "unconnected-(IC3-P0.5-Pad16)") (class "Default")
      (node (ref "IC3") (pin "16") (pinfunction "P0.5_16") (pintype "bidirectional"))
    )
    (net (code "77") (name "unconnected-(IC3-P0.6-Pad14)") (class "Default")
      (node (ref "IC3") (pin "14") (pinfunction "P0.6_14") (pintype "bidirectional"))
    )
    (net (code "78") (name "unconnected-(IC3-P0.7-Pad13)") (class "Default")
      (node (ref "IC3") (pin "13") (pinfunction "P0.7_13") (pintype "passive"))
    )
    (net (code "79") (name "unconnected-(IC3-P1.2{slash}T0{slash}SCL-Pad10)") (class "Default")
      (node (ref "IC3") (pin "10") (pinfunction "P1.2/T0/SCL_10") (pintype "bidirectional"))
    )
    (net (code "80") (name "unconnected-(IC3-P1.3{slash}INT0{slash}SDA-Pad9)") (class "Default")
      (node (ref "IC3") (pin "9") (pinfunction "P1.3/INT0/SDA_9") (pintype "bidirectional"))
    )
    (net (code "81") (name "unconnected-(IC3-P1.7-Pad2)") (class "Default")
      (node (ref "IC3") (pin "2") (pinfunction "P1.7_2") (pintype "bidirectional"))
    )
    (net (code "82") (name "unconnected-(IC3-P3.0{slash}XTAL2-Pad7)") (class "Default")
      (node (ref "IC3") (pin "7") (pinfunction "P3.0/XTAL2_7") (pintype "bidirectional"))
    )
    (net (code "83") (name "unconnected-(IC5-PIO0_2{slash}SSEL0{slash}CT16B0_CAP0-Pad10)") (class "Default")
      (node (ref "IC5") (pin "10") (pinfunction "PIO0_2/SSEL0/CT16B0_CAP0_10") (pintype "bidirectional"))
    )
    (net (code "84") (name "unconnected-(IC5-PIO0_3-Pad14)") (class "Default")
      (node (ref "IC5") (pin "14") (pinfunction "PIO0_3_14") (pintype "bidirectional"))
    )
    (net (code "85") (name "unconnected-(IC5-PIO1_11{slash}AD7{slash}CT32B1_CAP1-Pad42)") (class "Default")
      (node (ref "IC5") (pin "42") (pinfunction "PIO1_11/AD7/CT32B1_CAP1_42") (pintype "bidirectional"))
    )
    (net (code "86") (name "unconnected-(IC5-PIO2_1{slash}DSR{slash}SCK1-Pad13)") (class "Default")
      (node (ref "IC5") (pin "13") (pinfunction "PIO2_1/DSR/SCK1_13") (pintype "bidirectional"))
    )
    (net (code "87") (name "unconnected-(IC5-PIO2_4{slash}CT16B1_MAT1{slash}SSEL1-Pad19)") (class "Default")
      (node (ref "IC5") (pin "19") (pinfunction "PIO2_4/CT16B1_MAT1/SSEL1_19") (pintype "bidirectional"))
    )
    (net (code "88") (name "unconnected-(IC5-PIO2_5{slash}CT32B0_MAT0-Pad20)") (class "Default")
      (node (ref "IC5") (pin "20") (pinfunction "PIO2_5/CT32B0_MAT0_20") (pintype "bidirectional"))
    )
    (net (code "89") (name "unconnected-(IC5-PIO2_6{slash}CT32B0_MAT1-Pad1)") (class "Default")
      (node (ref "IC5") (pin "1") (pinfunction "PIO2_6/CT32B0_MAT1_1") (pintype "bidirectional"))
    )
    (net (code "90") (name "unconnected-(IC5-PIO2_7{slash}CT32B0_MAT2{slash}RXD-Pad11)") (class "Default")
      (node (ref "IC5") (pin "11") (pinfunction "PIO2_7/CT32B0_MAT2/RXD_11") (pintype "bidirectional"))
    )
    (net (code "91") (name "unconnected-(IC5-PIO2_8{slash}CT32B0_MAT3{slash}TXD-Pad12)") (class "Default")
      (node (ref "IC5") (pin "12") (pinfunction "PIO2_8/CT32B0_MAT3/TXD_12") (pintype "bidirectional"))
    )
    (net (code "92") (name "unconnected-(IC5-PIO2_10-Pad25)") (class "Default")
      (node (ref "IC5") (pin "25") (pinfunction "PIO2_10_25") (pintype "bidirectional"))
    )
    (net (code "93") (name "unconnected-(IC5-PIO3_3{slash}RI{slash}CT16B0_CAP0-Pad48)") (class "Default")
      (node (ref "IC5") (pin "48") (pinfunction "PIO3_3/RI/CT16B0_CAP0_48") (pintype "bidirectional"))
    )
    (net (code "94") (name "unconnected-(IC5-PIO3_4{slash}CT16B0_CAP1{slash}RXD-Pad18)") (class "Default")
      (node (ref "IC5") (pin "18") (pinfunction "PIO3_4/CT16B0_CAP1/RXD_18") (pintype "bidirectional"))
    )
    (net (code "95") (name "unconnected-(IC5-PIO3_5{slash}CT16B1_CAP1{slash}TXD-Pad21)") (class "Default")
      (node (ref "IC5") (pin "21") (pinfunction "PIO3_5/CT16B1_CAP1/TXD_21") (pintype "bidirectional"))
    )
    (net (code "96") (name "unconnected-(IC5-XTALOUT-Pad7)") (class "Default")
      (node (ref "IC5") (pin "7") (pinfunction "XTALOUT_7") (pintype "output"))
    )
    (net (code "97") (name "unconnected-(JP2-5V-Pad2)") (class "Default")
      (node (ref "JP2") (pin "2") (pinfunction "5V_2") (pintype "passive"))
    )
    (net (code "98") (name "unconnected-(JP2-5V-Pad4)") (class "Default")
      (node (ref "JP2") (pin "4") (pinfunction "5V_4") (pintype "passive"))
    )
    (net (code "99") (name "unconnected-(JP2-CE0{slash}IO8-Pad24)") (class "Default")
      (node (ref "JP2") (pin "24") (pinfunction "CE0/IO8_24") (pintype "passive"))
    )
    (net (code "100") (name "unconnected-(JP2-CE1{slash}IO7-Pad26)") (class "Default")
      (node (ref "JP2") (pin "26") (pinfunction "CE1/IO7_26") (pintype "passive"))
    )
    (net (code "101") (name "unconnected-(JP2-IO4-Pad7)") (class "Default")
      (node (ref "JP2") (pin "7") (pinfunction "IO4_7") (pintype "passive"))
    )
    (net (code "102") (name "unconnected-(JP2-IO5-Pad29)") (class "Default")
      (node (ref "JP2") (pin "29") (pinfunction "IO5_29") (pintype "bidirectional"))
    )
    (net (code "103") (name "unconnected-(JP2-IO6-Pad31)") (class "Default")
      (node (ref "JP2") (pin "31") (pinfunction "IO6_31") (pintype "bidirectional"))
    )
    (net (code "104") (name "unconnected-(JP2-IO9{slash}MISO-Pad21)") (class "Default")
      (node (ref "JP2") (pin "21") (pinfunction "IO9/MISO_21") (pintype "passive"))
    )
    (net (code "105") (name "unconnected-(JP2-IO10{slash}MOSI-Pad19)") (class "Default")
      (node (ref "JP2") (pin "19") (pinfunction "IO10/MOSI_19") (pintype "passive"))
    )
    (net (code "106") (name "unconnected-(JP2-IO11{slash}SCK-Pad23)") (class "Default")
      (node (ref "JP2") (pin "23") (pinfunction "IO11/SCK_23") (pintype "passive"))
    )
    (net (code "107") (name "unconnected-(JP2-IO12-Pad32)") (class "Default")
      (node (ref "JP2") (pin "32") (pinfunction "IO12_32") (pintype "bidirectional"))
    )
    (net (code "108") (name "unconnected-(JP2-IO13-Pad33)") (class "Default")
      (node (ref "JP2") (pin "33") (pinfunction "IO13_33") (pintype "bidirectional"))
    )
    (net (code "109") (name "unconnected-(JP2-IO16-Pad36)") (class "Default")
      (node (ref "JP2") (pin "36") (pinfunction "IO16_36") (pintype "bidirectional"))
    )
    (net (code "110") (name "unconnected-(JP2-IO17-Pad11)") (class "Default")
      (node (ref "JP2") (pin "11") (pinfunction "IO17_11") (pintype "passive"))
    )
    (net (code "111") (name "unconnected-(JP2-IO19-Pad35)") (class "Default")
      (node (ref "JP2") (pin "35") (pinfunction "IO19_35") (pintype "bidirectional"))
    )
    (net (code "112") (name "unconnected-(JP2-IO20-Pad38)") (class "Default")
      (node (ref "JP2") (pin "38") (pinfunction "IO20_38") (pintype "bidirectional"))
    )
    (net (code "113") (name "unconnected-(JP2-IO21-Pad40)") (class "Default")
      (node (ref "JP2") (pin "40") (pinfunction "IO21_40") (pintype "bidirectional"))
    )
    (net (code "114") (name "unconnected-(JP2-IO22-Pad15)") (class "Default")
      (node (ref "JP2") (pin "15") (pinfunction "IO22_15") (pintype "passive"))
    )
    (net (code "115") (name "unconnected-(JP2-IO23-Pad16)") (class "Default")
      (node (ref "JP2") (pin "16") (pinfunction "IO23_16") (pintype "passive"))
    )
    (net (code "116") (name "unconnected-(JP2-IO24-Pad18)") (class "Default")
      (node (ref "JP2") (pin "18") (pinfunction "IO24_18") (pintype "passive"))
    )
    (net (code "117") (name "unconnected-(JP2-IO25-Pad22)") (class "Default")
      (node (ref "JP2") (pin "22") (pinfunction "IO25_22") (pintype "passive"))
    )
    (net (code "118") (name "unconnected-(JP2-IO26-Pad37)") (class "Default")
      (node (ref "JP2") (pin "37") (pinfunction "IO26_37") (pintype "bidirectional"))
    )
    (net (code "119") (name "unconnected-(JP2-IO27-Pad13)") (class "Default")
      (node (ref "JP2") (pin "13") (pinfunction "IO27_13") (pintype "passive"))
    )
    (net (code "120") (name "unconnected-(JP2-PWM{slash}IO18-Pad12)") (class "Default")
      (node (ref "JP2") (pin "12") (pinfunction "PWM/IO18_12") (pintype "passive"))
    )
    (net (code "121") (name "unconnected-(JP7-Pad6)") (class "Default")
      (node (ref "JP7") (pin "6") (pinfunction "6_6") (pintype "passive"))
    )
    (net (code "122") (name "unconnected-(JP7-Pad8)") (class "Default")
      (node (ref "JP7") (pin "8") (pinfunction "8_8") (pintype "passive"))
    )
  )
)
